# AstroEQ_PTH_V4_8.net
KiCad netlist of a schematic drawn in EAGLE
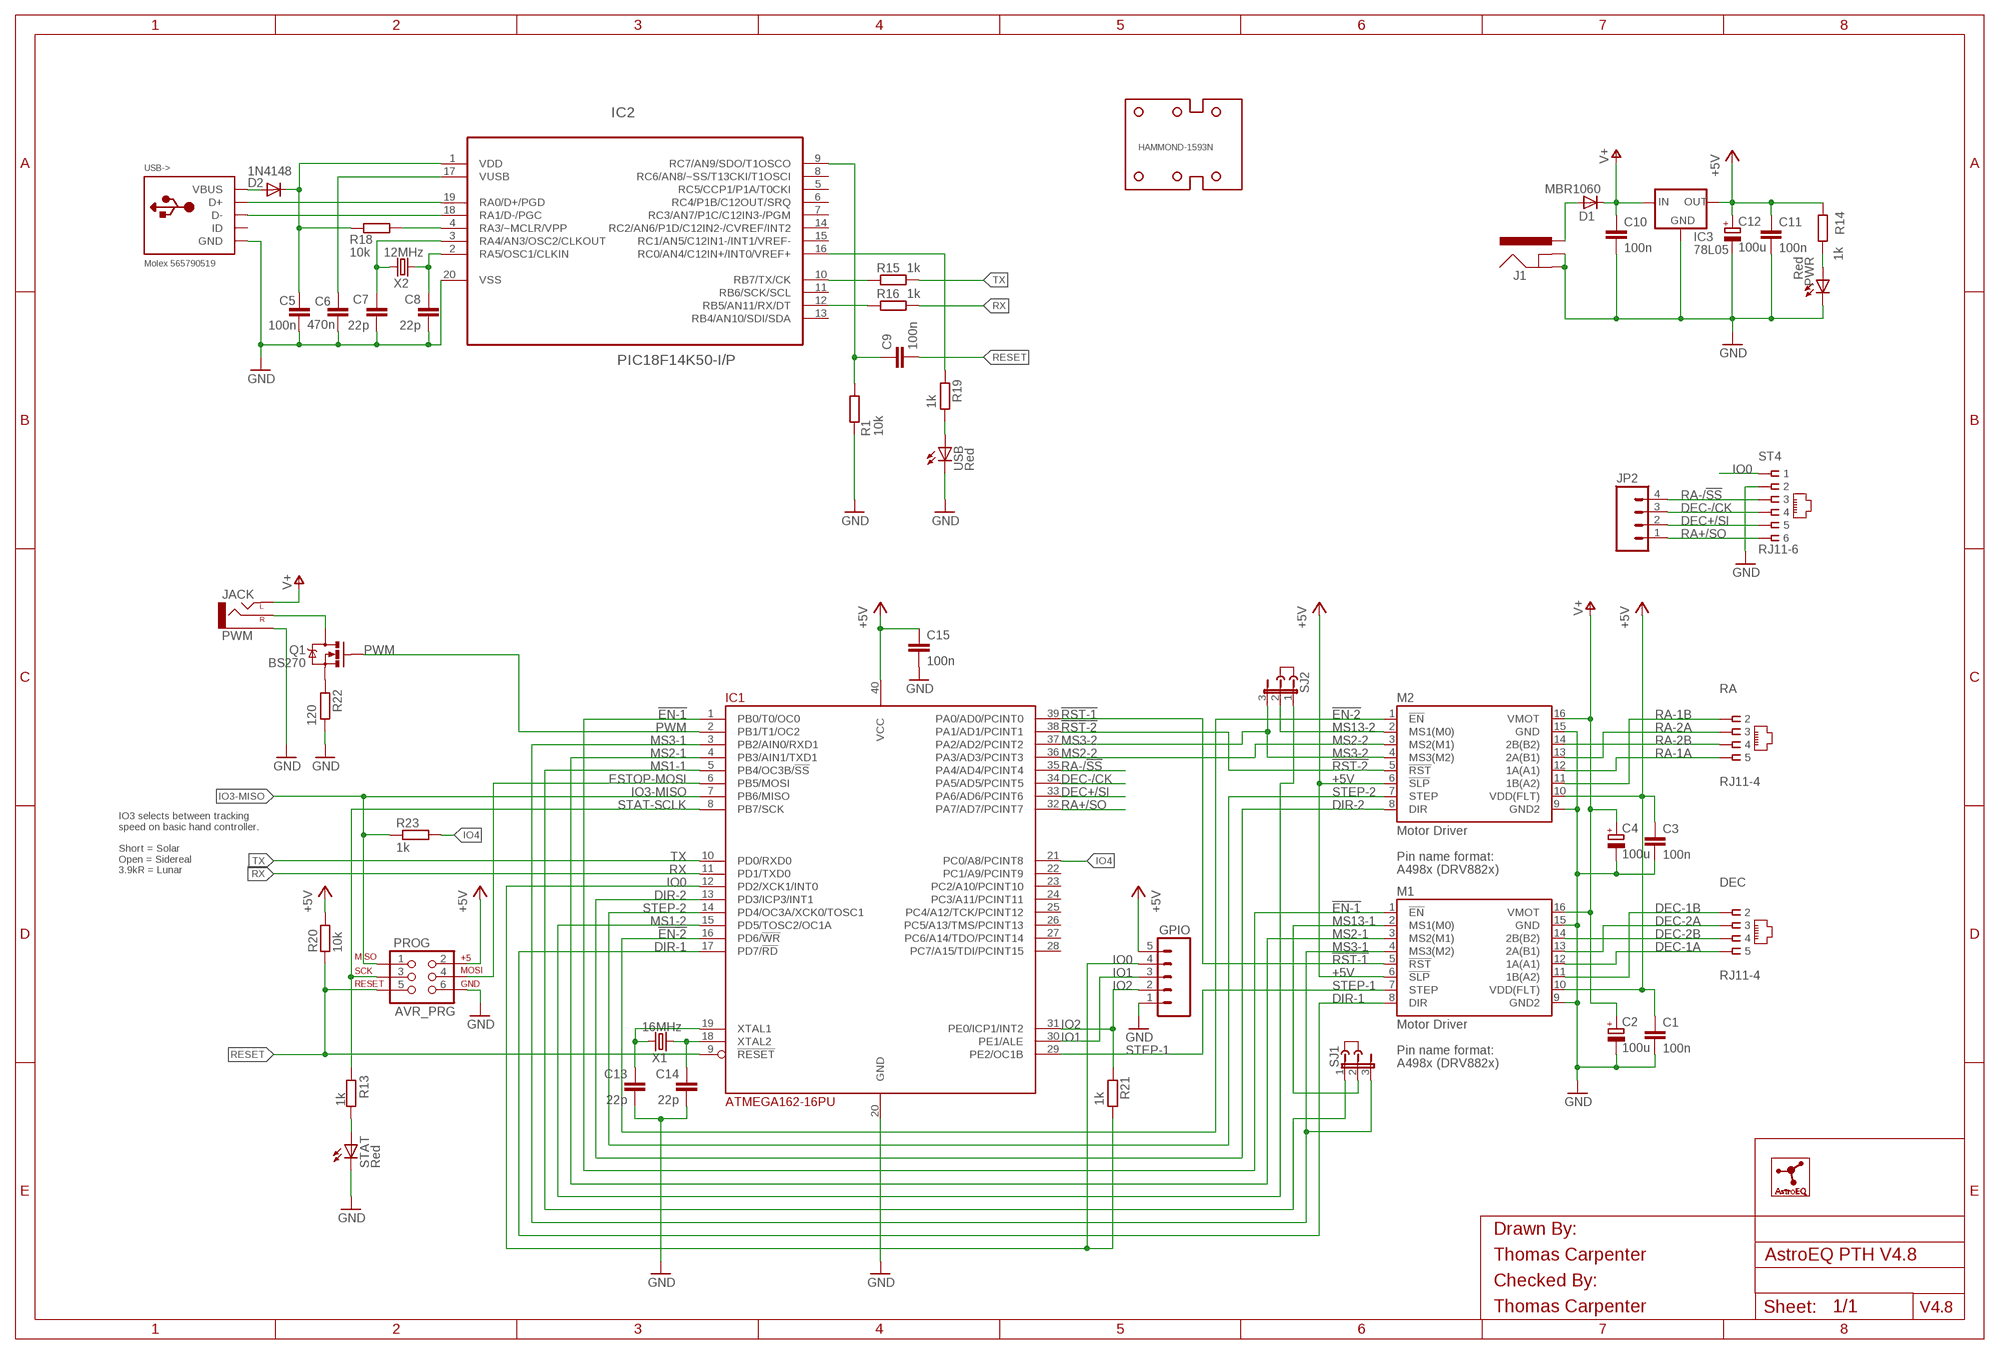
[diagram p0: schematic, sheet 1]

(export (version "E")
  (design (tool "Eeschema 10.0.6"))
  (components
    (comp (ref "C1")
      (value "100n")
      (footprint "eagle-import:C025-024X044")
      (fields (field (name "MF") "AVX") (field (name "MPN") "SR205C104KAR"))
      (libsource (lib "eagle-import") (part "C-EU025-024X044"))
    )
    (comp (ref "C2")
      (value "100u")
      (footprint "eagle-import:E2,5-7")
      (fields (field (name "MF") "MULTICOMP") (field (name "MPN") "MCGPR25V107M6.3X11"))
      (libsource (lib "eagle-import") (part "CPOL-EUE2.5-7"))
    )
    (comp (ref "C3")
      (value "100n")
      (footprint "eagle-import:C025-024X044")
      (fields (field (name "MF") "AVX") (field (name "MPN") "SR205C104KAR"))
      (libsource (lib "eagle-import") (part "C-EU025-024X044"))
    )
    (comp (ref "C4")
      (value "100u")
      (footprint "eagle-import:E2,5-7")
      (fields (field (name "MF") "MULTICOMP") (field (name "MPN") "MCGPR25V107M6.3X11"))
      (libsource (lib "eagle-import") (part "CPOL-EUE2.5-7"))
    )
    (comp (ref "C5")
      (value "100n")
      (footprint "eagle-import:C025-024X044")
      (fields (field (name "MF") "AVX") (field (name "MPN") "SR205C104KAR"))
      (libsource (lib "eagle-import") (part "C-EU025-024X044"))
    )
    (comp (ref "C6")
      (value "470n")
      (footprint "eagle-import:C025-024X044")
      (fields (field (name "MF") "KEMET") (field (name "MPN") "C320C474M5U5TA"))
      (libsource (lib "eagle-import") (part "C-EU025-024X044"))
    )
    (comp (ref "C7")
      (value "22p")
      (footprint "eagle-import:C025-024X044")
      (fields (field (name "MF") "AVX") (field (name "MPN") "SR151A220JAR"))
      (libsource (lib "eagle-import") (part "C-EU025-024X044"))
    )
    (comp (ref "C8")
      (value "22p")
      (footprint "eagle-import:C025-024X044")
      (fields (field (name "MF") "AVX") (field (name "MPN") "SR151A220JAR"))
      (libsource (lib "eagle-import") (part "C-EU025-024X044"))
    )
    (comp (ref "C9")
      (value "100n")
      (footprint "eagle-import:C025-024X044")
      (fields (field (name "MF") "AVX") (field (name "MPN") "SR205C104KAR"))
      (libsource (lib "eagle-import") (part "C-EU025-024X044"))
    )
    (comp (ref "C10")
      (value "100n")
      (footprint "eagle-import:C025-024X044")
      (fields (field (name "MF") "AVX") (field (name "MPN") "SR205C104KAR"))
      (libsource (lib "eagle-import") (part "C-EU025-024X044"))
    )
    (comp (ref "C11")
      (value "100n")
      (footprint "eagle-import:C025-024X044")
      (fields (field (name "MF") "AVX") (field (name "MPN") "SR205C104KAR"))
      (libsource (lib "eagle-import") (part "C-EU025-024X044"))
    )
    (comp (ref "C12")
      (value "100u")
      (footprint "eagle-import:E2,5-7")
      (fields (field (name "MF") "MULTICOMP") (field (name "MPN") "MCGPR25V107M6.3X11"))
      (libsource (lib "eagle-import") (part "CPOL-EUE2.5-7"))
    )
    (comp (ref "C13")
      (value "22p")
      (footprint "eagle-import:C025-024X044")
      (fields (field (name "MF") "AVX") (field (name "MPN") "SR151A220JAR"))
      (libsource (lib "eagle-import") (part "C-EU025-024X044"))
    )
    (comp (ref "C14")
      (value "22p")
      (footprint "eagle-import:C025-024X044")
      (fields (field (name "MF") "AVX") (field (name "MPN") "SR151A220JAR"))
      (libsource (lib "eagle-import") (part "C-EU025-024X044"))
    )
    (comp (ref "C15")
      (value "100n")
      (footprint "eagle-import:C025-024X044")
      (fields (field (name "MF") "AVX") (field (name "MPN") "SR205C104KAR"))
      (libsource (lib "eagle-import") (part "C-EU025-024X044"))
    )
    (comp (ref "D1")
      (value "MBR1060")
      (footprint "eagle-import:C221B1A")
      (fields (field (name "MF") "MULTICOMP"))
      (libsource (lib "eagle-import") (part "MUR820"))
    )
    (comp (ref "D2")
      (value "1N4148")
      (footprint "eagle-import:DIODE-1N4148")
      (fields (field (name "MF") "MULTICOMP") (field (name "MPN") "1N4148."))
      (libsource (lib "eagle-import") (part "DIODE1N4148"))
    )
    (comp (ref "DEC")
      (value "RJ11-4")
      (footprint "eagle-import:RJ11-NO_SHIELD-4")
      (fields (field (name "MF") "MOLEX") (field (name "MPN") "95501-2641"))
      (libsource (lib "eagle-import") (part "RJ11-4"))
    )
    (comp (ref "GPIO")
      (value "M05PTH")
      (footprint "eagle-import:1X05")
      (fields (field (name "MF") "CYNERGY3") (field (name "MPN") "SSF211X050"))
      (libsource (lib "eagle-import") (part "M05PTH"))
    )
    (comp (ref "HAMMOND-1593N")
      (value "HAMMOND-1593N-4HOLE")
      (footprint "eagle-import:HAMMOND-1593N4HOLES")
      (fields (field (name "MF") "HAMMOND") (field (name "MPN") "1593NBK"))
      (libsource (lib "eagle-import") (part "HAMMOND-1593N-4HOLE"))
    )
    (comp (ref "IC1")
      (value "ATMEGA162-16PU")
      (footprint "eagle-import:DIL40")
      (fields (field (name "MF") "ATMEL"))
      (libsource (lib "eagle-import") (part "ATMEGA162-16PU"))
    )
    (comp (ref "IC2")
      (value "PIC18F14K50-I/P")
      (footprint "eagle-import:DIL20")
      (fields (field (name "MF") "MICROCHIP"))
      (libsource (lib "eagle-import") (part "PIC18F14K50-I/P"))
    )
    (comp (ref "IC3")
      (value "78L05")
      (footprint "eagle-import:TO-92")
      (fields (field (name "MF") "FAIRCHILD SEMICONDUCTOR") (field (name "MPN") "LM78L05ACZX"))
      (libsource (lib "eagle-import") (part "V_REG_78XXTO-92"))
    )
    (comp (ref "J1")
      (value "POWER_JACKPTH")
      (footprint "eagle-import:POWER_JACK_PTH")
      (fields (field (name "MF") "MULTICOMP") (field (name "MPN") "MJ-179PH"))
      (libsource (lib "eagle-import") (part "POWER_JACKPTH"))
    )
    (comp (ref "J2")
      (value "JUMPER")
      (footprint "eagle-import:JUMP")
      (libsource (lib "eagle-import") (part "JUMPER"))
    )
    (comp (ref "J3")
      (value "JUMPER")
      (footprint "eagle-import:JUMP")
      (libsource (lib "eagle-import") (part "JUMPER"))
    )
    (comp (ref "JP2")
      (value "M04PTH")
      (footprint "eagle-import:1X04")
      (libsource (lib "eagle-import") (part "M04PTH"))
    )
    (comp (ref "LOGO1")
      (value "ASTROEQ5MM")
      (footprint "eagle-import:ASTROEQ-SMALL")
      (libsource (lib "eagle-import") (part "ASTROEQ5MM"))
    )
    (comp (ref "M1")
      (value "Motor Driver")
      (footprint "eagle-import:DIP16-W")
      (fields (field (name "MF") "SAMTEC") (field (name "MPN") "CES-116-01-T-S"))
      (libsource (lib "eagle-import") (part "A4983CARRIER"))
    )
    (comp (ref "M2")
      (value "Motor Driver")
      (footprint "eagle-import:DIP16-W")
      (fields (field (name "MF") "SAMTEC") (field (name "MPN") "CES-116-01-T-S"))
      (libsource (lib "eagle-import") (part "A4983CARRIER"))
    )
    (comp (ref "PROG")
      (value "AVR_PRG")
      (footprint "eagle-import:2X3")
      (fields (field (name "MF") "TE CONNECTIVITY / AMP") (field (name "MPN") "826632-3"))
      (libsource (lib "eagle-import") (part "AVR_SPI_PRG_6PTH"))
    )
    (comp (ref "PWM")
      (value "JACK")
      (footprint "eagle-import:AUDIO-JACK")
      (fields (field (name "MF") "CLIFF ELECTRONIC COMPONENTS") (field (name "MPN") "FC68131"))
      (libsource (lib "eagle-import") (part "AUDIO-JACKPTH"))
    )
    (comp (ref "PWR")
      (value "Red")
      (footprint "eagle-import:LED3MM")
      (fields (field (name "MF") "KINGBRIGHT") (field (name "MPN") "L-424HDT"))
      (libsource (lib "eagle-import") (part "LED3MM"))
    )
    (comp (ref "Q1")
      (value "BS270")
      (footprint "eagle-import:TO-92")
      (fields (field (name "MF") "FAIRCHILD SEMICONDUCTOR"))
      (libsource (lib "eagle-import") (part "MOSFET-NCHANNELPTH"))
    )
    (comp (ref "R1")
      (value "10k")
      (footprint "eagle-import:0204_7")
      (fields (field (name "MF") "MULTICOMP") (field (name "MPN") "MF12 10K"))
      (libsource (lib "eagle-import") (part "R-EU_0204/7"))
    )
    (comp (ref "R13")
      (value "1k")
      (footprint "eagle-import:0204_7")
      (fields (field (name "MF") "MULTICOMP") (field (name "MPN") "MF12 1K"))
      (libsource (lib "eagle-import") (part "R-EU_0204/7"))
    )
    (comp (ref "R14")
      (value "1k")
      (footprint "eagle-import:0204_7")
      (fields (field (name "MF") "MULTICOMP") (field (name "MPN") "MF12 1K"))
      (libsource (lib "eagle-import") (part "R-EU_0204/7"))
    )
    (comp (ref "R15")
      (value "1k")
      (footprint "eagle-import:0204_7")
      (fields (field (name "MF") "MULTICOMP") (field (name "MPN") "MF12 1K"))
      (libsource (lib "eagle-import") (part "R-EU_0204/7"))
    )
    (comp (ref "R16")
      (value "1k")
      (footprint "eagle-import:0204_7")
      (fields (field (name "MF") "MULTICOMP") (field (name "MPN") "MF12 1K"))
      (libsource (lib "eagle-import") (part "R-EU_0204/7"))
    )
    (comp (ref "R18")
      (value "10k")
      (footprint "eagle-import:0204_7")
      (fields (field (name "MF") "MULTICOMP") (field (name "MPN") "MF12 10K"))
      (libsource (lib "eagle-import") (part "R-EU_0204/7"))
    )
    (comp (ref "R19")
      (value "1k")
      (footprint "eagle-import:0204_7")
      (fields (field (name "MF") "MULTICOMP") (field (name "MPN") "MF12 1K"))
      (libsource (lib "eagle-import") (part "R-EU_0204/7"))
    )
    (comp (ref "R20")
      (value "10k")
      (footprint "eagle-import:0204_7")
      (fields (field (name "MF") "MULTICOMP") (field (name "MPN") "MF12 10K"))
      (libsource (lib "eagle-import") (part "R-EU_0204/7"))
    )
    (comp (ref "R21")
      (value "1k")
      (footprint "eagle-import:0204_7")
      (fields (field (name "MF") "MULTICOMP") (field (name "MPN") "MF12 1K"))
      (libsource (lib "eagle-import") (part "R-EU_0204/7"))
    )
    (comp (ref "R22")
      (value "120")
      (footprint "eagle-import:0204_7")
      (fields (field (name "MF") "MULTICOMP") (field (name "MPN") "MF12 120R"))
      (libsource (lib "eagle-import") (part "R-EU_0204/7"))
    )
    (comp (ref "R23")
      (value "1k")
      (footprint "eagle-import:0207_10")
      (fields (field (name "MF") "MULTICOMP") (field (name "MPN") "MF12 1K"))
      (libsource (lib "eagle-import") (part "R-EU_0207/10"))
    )
    (comp (ref "RA")
      (value "RJ11-4")
      (footprint "eagle-import:RJ11-NO_SHIELD-4")
      (fields (field (name "MF") "MOLEX") (field (name "MPN") "95501-2641"))
      (libsource (lib "eagle-import") (part "RJ11-4"))
    )
    (comp (ref "SJ1")
      (value "JP2EL")
      (footprint "eagle-import:JP2L")
      (libsource (lib "eagle-import") (part "JP2EL"))
    )
    (comp (ref "SJ2")
      (value "JP2EL")
      (footprint "eagle-import:JP2L")
      (libsource (lib "eagle-import") (part "JP2EL"))
    )
    (comp (ref "ST4")
      (value "RJ11-6")
      (footprint "eagle-import:RJ11-NO_SHIELD")
      (fields
        (field (name "MF") "TYCO ELECTRONICS")
        (field (name "MPN") "RJ11-2L-B")
        (field (name "MF_1") "MOLEX")
        (field (name "MPN_1") "95501-2661")
        (field (name "OC_FARNELL") "1536490")
      )
      (libsource (lib "eagle-import") (part "RJ11-2L-B"))
    )
    (comp (ref "STAT")
      (value "Red")
      (footprint "eagle-import:LED3MM")
      (fields (field (name "MF") "KINGBRIGHT") (field (name "MPN") "L-424HDT"))
      (libsource (lib "eagle-import") (part "LED3MM"))
    )
    (comp (ref "USB")
      (value "Red")
      (footprint "eagle-import:LED3MM")
      (fields (field (name "MF") "KINGBRIGHT") (field (name "MPN") "L-424HDT"))
      (libsource (lib "eagle-import") (part "LED3MM"))
    )
    (comp (ref "USB->")
      (value "Molex 565790519")
      (footprint "eagle-import:USB-MINIB-THM-MOLEX")
      (fields (field (name "MF") "MOLEX") (field (name "MPN") "565790519"))
      (libsource (lib "eagle-import") (part "USBMOLEX"))
    )
    (comp (ref "X1")
      (value "16MHz")
      (footprint "eagle-import:HC49US")
      (fields (field (name "MF") "TXC") (field (name "MPN") "9B-16.000MEEJ-B"))
      (libsource (lib "eagle-import") (part "CRYSTALHC49US"))
    )
    (comp (ref "X2")
      (value "12MHz")
      (footprint "eagle-import:HC49US")
      (fields (field (name "MF") "TXC") (field (name "MPN") "9B-12.000MAAJ-B"))
      (libsource (lib "eagle-import") (part "CRYSTALHC49US"))
    )
  )
  (nets
    (net (code "1") (name "+5V") (class "Default")
      (node (ref "C1") (pin "1") (pinfunction "1_1") (pintype "passive"))
      (node (ref "C11") (pin "1") (pinfunction "1_1") (pintype "passive"))
      (node (ref "C12") (pin "+") (pinfunction "+_+") (pintype "passive"))
      (node (ref "C15") (pin "1") (pinfunction "1_1") (pintype "passive"))
      (node (ref "C3") (pin "1") (pinfunction "1_1") (pintype "passive"))
      (node (ref "GPIO") (pin "5") (pinfunction "5_5") (pintype "passive"))
      (node (ref "IC1") (pin "40") (pinfunction "VCC_40") (pintype "power_in"))
      (node (ref "IC3") (pin "1") (pinfunction "OUT_1") (pintype "power_in"))
      (node (ref "M1") (pin "10") (pinfunction "VDD(FLT)_10") (pintype "power_in"))
      (node (ref "M1") (pin "6") (pinfunction "~{SLP}_6") (pintype "input"))
      (node (ref "M2") (pin "10") (pinfunction "VDD(FLT)_10") (pintype "power_in"))
      (node (ref "M2") (pin "6") (pinfunction "~{SLP}_6") (pintype "input"))
      (node (ref "PROG") (pin "2") (pinfunction "2_2") (pintype "passive"))
      (node (ref "R14") (pin "1") (pinfunction "1_1") (pintype "passive"))
      (node (ref "R20") (pin "2") (pinfunction "2_2") (pintype "passive"))
    )
    (net (code "2") (name "/DEC+{slash}SI") (class "Default")
      (node (ref "IC1") (pin "33") (pinfunction "PA6/AD6/PCINT6_33") (pintype "bidirectional"))
      (node (ref "JP2") (pin "2") (pinfunction "2_2") (pintype "passive"))
      (node (ref "ST4") (pin "5") (pinfunction "5_5") (pintype "passive"))
    )
    (net (code "3") (name "/DEC-1A") (class "Default")
      (node (ref "DEC") (pin "5") (pinfunction "5_5") (pintype "passive"))
      (node (ref "M1") (pin "12") (pinfunction "1A(A1)_12") (pintype "output"))
    )
    (net (code "4") (name "/DEC-1B") (class "Default")
      (node (ref "DEC") (pin "2") (pinfunction "2_2") (pintype "passive"))
      (node (ref "M1") (pin "11") (pinfunction "1B(A2)_11") (pintype "output"))
    )
    (net (code "5") (name "/DEC-2A") (class "Default")
      (node (ref "DEC") (pin "3") (pinfunction "3_3") (pintype "passive"))
      (node (ref "M1") (pin "13") (pinfunction "2A(B1)_13") (pintype "output"))
    )
    (net (code "6") (name "/DEC-2B") (class "Default")
      (node (ref "DEC") (pin "4") (pinfunction "4_4") (pintype "passive"))
      (node (ref "M1") (pin "14") (pinfunction "2B(B2)_14") (pintype "output"))
    )
    (net (code "7") (name "/DEC-{slash}CK") (class "Default")
      (node (ref "IC1") (pin "34") (pinfunction "PA5/AD5/PCINT5_34") (pintype "bidirectional"))
      (node (ref "JP2") (pin "3") (pinfunction "3_3") (pintype "passive"))
      (node (ref "ST4") (pin "4") (pinfunction "4_4") (pintype "passive"))
    )
    (net (code "8") (name "/DIR-1") (class "Default")
      (node (ref "IC1") (pin "17") (pinfunction "PD7/~{RD}_17") (pintype "bidirectional"))
      (node (ref "M1") (pin "8") (pinfunction "DIR_8") (pintype "input"))
    )
    (net (code "9") (name "/DIR-2") (class "Default")
      (node (ref "IC1") (pin "13") (pinfunction "PD3/ICP3/INT1_13") (pintype "bidirectional"))
      (node (ref "M2") (pin "8") (pinfunction "DIR_8") (pintype "input"))
    )
    (net (code "10") (name "/ESTOP-MOSI") (class "Default")
      (node (ref "IC1") (pin "6") (pinfunction "PB5/MOSI_6") (pintype "bidirectional"))
      (node (ref "PROG") (pin "4") (pinfunction "4_4") (pintype "passive"))
    )
    (net (code "11") (name "/IO0") (class "Default")
      (node (ref "GPIO") (pin "4") (pinfunction "4_4") (pintype "passive"))
      (node (ref "IC1") (pin "12") (pinfunction "PD2/XCK1/INT0_12") (pintype "bidirectional"))
      (node (ref "R21") (pin "1") (pinfunction "1_1") (pintype "passive"))
      (node (ref "ST4") (pin "1") (pinfunction "1_1") (pintype "passive"))
    )
    (net (code "12") (name "/IO1") (class "Default")
      (node (ref "GPIO") (pin "3") (pinfunction "3_3") (pintype "passive"))
      (node (ref "IC1") (pin "30") (pinfunction "PE1/ALE_30") (pintype "bidirectional"))
    )
    (net (code "13") (name "/IO2") (class "Default")
      (node (ref "GPIO") (pin "2") (pinfunction "2_2") (pintype "passive"))
      (node (ref "IC1") (pin "31") (pinfunction "PE0/ICP1/INT2_31") (pintype "bidirectional"))
      (node (ref "R21") (pin "2") (pinfunction "2_2") (pintype "passive"))
    )
    (net (code "14") (name "/MS1-1") (class "Default")
      (node (ref "IC1") (pin "5") (pinfunction "PB4/OC3B/~{SS}_5") (pintype "bidirectional"))
      (node (ref "SJ1") (pin "1") (pinfunction "1_1") (pintype "passive"))
    )
    (net (code "15") (name "/MS1-2") (class "Default")
      (node (ref "IC1") (pin "15") (pinfunction "PD5/TOSC2/OC1A_15") (pintype "bidirectional"))
      (node (ref "SJ2") (pin "1") (pinfunction "1_1") (pintype "passive"))
    )
    (net (code "16") (name "/MS2-1") (class "Default")
      (node (ref "IC1") (pin "4") (pinfunction "PB3/AIN1/TXD1_4") (pintype "bidirectional"))
      (node (ref "M1") (pin "3") (pinfunction "MS2(M1)_3") (pintype "input"))
    )
    (net (code "17") (name "/MS2-2") (class "Default")
      (node (ref "IC1") (pin "36") (pinfunction "PA3/AD3/PCINT3_36") (pintype "bidirectional"))
      (node (ref "M2") (pin "3") (pinfunction "MS2(M1)_3") (pintype "input"))
    )
    (net (code "18") (name "/MS3-1") (class "Default")
      (node (ref "IC1") (pin "3") (pinfunction "PB2/AIN0/RXD1_3") (pintype "bidirectional"))
      (node (ref "M1") (pin "4") (pinfunction "MS3(M2)_4") (pintype "input"))
      (node (ref "SJ1") (pin "3") (pinfunction "3_3") (pintype "passive"))
    )
    (net (code "19") (name "/MS3-2") (class "Default")
      (node (ref "IC1") (pin "37") (pinfunction "PA2/AD2/PCINT2_37") (pintype "bidirectional"))
      (node (ref "M2") (pin "4") (pinfunction "MS3(M2)_4") (pintype "input"))
      (node (ref "SJ2") (pin "3") (pinfunction "3_3") (pintype "passive"))
    )
    (net (code "20") (name "/MS13-1") (class "Default")
      (node (ref "M1") (pin "2") (pinfunction "MS1(M0)_2") (pintype "input"))
      (node (ref "SJ1") (pin "2") (pinfunction "2_2") (pintype "passive"))
    )
    (net (code "21") (name "/MS13-2") (class "Default")
      (node (ref "M2") (pin "2") (pinfunction "MS1(M0)_2") (pintype "input"))
      (node (ref "SJ2") (pin "2") (pinfunction "2_2") (pintype "passive"))
    )
    (net (code "22") (name "/PWM") (class "Default")
      (node (ref "IC1") (pin "2") (pinfunction "PB1/T1/OC2_2") (pintype "bidirectional"))
      (node (ref "Q1") (pin "2") (pinfunction "G_2") (pintype "passive"))
    )
    (net (code "23") (name "/RA+{slash}SO") (class "Default")
      (node (ref "IC1") (pin "32") (pinfunction "PA7/AD7/PCINT7_32") (pintype "bidirectional"))
      (node (ref "JP2") (pin "1") (pinfunction "1_1") (pintype "passive"))
      (node (ref "ST4") (pin "6") (pinfunction "6_6") (pintype "passive"))
    )
    (net (code "24") (name "/RA-1A") (class "Default")
      (node (ref "M2") (pin "12") (pinfunction "1A(A1)_12") (pintype "output"))
      (node (ref "RA") (pin "5") (pinfunction "5_5") (pintype "passive"))
    )
    (net (code "25") (name "/RA-1B") (class "Default")
      (node (ref "M2") (pin "11") (pinfunction "1B(A2)_11") (pintype "output"))
      (node (ref "RA") (pin "2") (pinfunction "2_2") (pintype "passive"))
    )
    (net (code "26") (name "/RA-2A") (class "Default")
      (node (ref "M2") (pin "13") (pinfunction "2A(B1)_13") (pintype "output"))
      (node (ref "RA") (pin "3") (pinfunction "3_3") (pintype "passive"))
    )
    (net (code "27") (name "/RA-2B") (class "Default")
      (node (ref "M2") (pin "14") (pinfunction "2B(B2)_14") (pintype "output"))
      (node (ref "RA") (pin "4") (pinfunction "4_4") (pintype "passive"))
    )
    (net (code "28") (name "/RA-{slash}~{SS}") (class "Default")
      (node (ref "IC1") (pin "35") (pinfunction "PA4/AD4/PCINT4_35") (pintype "bidirectional"))
      (node (ref "JP2") (pin "4") (pinfunction "4_4") (pintype "passive"))
      (node (ref "ST4") (pin "3") (pinfunction "3_3") (pintype "passive"))
    )
    (net (code "29") (name "/STAT-SCLK") (class "Default")
      (node (ref "IC1") (pin "8") (pinfunction "PB7/SCK_8") (pintype "bidirectional"))
      (node (ref "PROG") (pin "3") (pinfunction "3_3") (pintype "passive"))
      (node (ref "R13") (pin "1") (pinfunction "1_1") (pintype "passive"))
    )
    (net (code "30") (name "/STEP-1") (class "Default")
      (node (ref "IC1") (pin "29") (pinfunction "PE2/OC1B_29") (pintype "bidirectional"))
      (node (ref "M1") (pin "7") (pinfunction "STEP_7") (pintype "input"))
    )
    (net (code "31") (name "/STEP-2") (class "Default")
      (node (ref "IC1") (pin "14") (pinfunction "PD4/OC3A/XCK0/TOSC1_14") (pintype "bidirectional"))
      (node (ref "M2") (pin "7") (pinfunction "STEP_7") (pintype "input"))
    )
    (net (code "32") (name "/~{EN-1}") (class "Default")
      (node (ref "IC1") (pin "1") (pinfunction "PB0/T0/OC0_1") (pintype "bidirectional"))
      (node (ref "M1") (pin "1") (pinfunction "~{EN}_1") (pintype "input"))
    )
    (net (code "33") (name "/~{EN-2}") (class "Default")
      (node (ref "IC1") (pin "16") (pinfunction "PD6/~{WR}_16") (pintype "bidirectional"))
      (node (ref "M2") (pin "1") (pinfunction "~{EN}_1") (pintype "input"))
    )
    (net (code "34") (name "/~{RST-1}") (class "Default")
      (node (ref "IC1") (pin "39") (pinfunction "PA0/AD0/PCINT0_39") (pintype "bidirectional"))
      (node (ref "M1") (pin "5") (pinfunction "~{RST}_5") (pintype "input"))
    )
    (net (code "35") (name "/~{RST-2}") (class "Default")
      (node (ref "IC1") (pin "38") (pinfunction "PA1/AD1/PCINT1_38") (pintype "bidirectional"))
      (node (ref "M2") (pin "5") (pinfunction "~{RST}_5") (pintype "input"))
    )
    (net (code "36") (name "GND") (class "Default")
      (node (ref "C1") (pin "2") (pinfunction "2_2") (pintype "passive"))
      (node (ref "C10") (pin "2") (pinfunction "2_2") (pintype "passive"))
      (node (ref "C11") (pin "2") (pinfunction "2_2") (pintype "passive"))
      (node (ref "C12") (pin "-") (pinfunction "-_-") (pintype "passive"))
      (node (ref "C13") (pin "2") (pinfunction "2_2") (pintype "passive"))
      (node (ref "C14") (pin "2") (pinfunction "2_2") (pintype "passive"))
      (node (ref "C15") (pin "2") (pinfunction "2_2") (pintype "passive"))
      (node (ref "C2") (pin "-") (pinfunction "-_-") (pintype "passive"))
      (node (ref "C3") (pin "2") (pinfunction "2_2") (pintype "passive"))
      (node (ref "C4") (pin "-") (pinfunction "-_-") (pintype "passive"))
      (node (ref "C5") (pin "2") (pinfunction "2_2") (pintype "passive"))
      (node (ref "C6") (pin "1") (pinfunction "1_1") (pintype "passive"))
      (node (ref "C7") (pin "2") (pinfunction "2_2") (pintype "passive"))
      (node (ref "C8") (pin "2") (pinfunction "2_2") (pintype "passive"))
      (node (ref "GPIO") (pin "1") (pinfunction "1_1") (pintype "passive"))
      (node (ref "IC1") (pin "20") (pinfunction "GND_20") (pintype "power_in"))
      (node (ref "IC2") (pin "20") (pinfunction "VSS_20") (pintype "power_in"))
      (node (ref "IC3") (pin "2") (pinfunction "GND_2") (pintype "input"))
      (node (ref "J1") (pin "GND") (pinfunction "GND_GND") (pintype "bidirectional"))
      (node (ref "J1") (pin "GNDBREAK") (pinfunction "GNDBREAK_GNDBREAK") (pintype "bidirectional"))
      (node (ref "M1") (pin "15") (pinfunction "GND_15") (pintype "power_in"))
      (node (ref "M1") (pin "9") (pinfunction "GND2_9") (pintype "power_in"))
      (node (ref "M2") (pin "15") (pinfunction "GND_15") (pintype "power_in"))
      (node (ref "M2") (pin "9") (pinfunction "GND2_9") (pintype "power_in"))
      (node (ref "PROG") (pin "6") (pinfunction "6_6") (pintype "passive"))
      (node (ref "PWM") (pin "SLEEVE") (pinfunction "SLEEVE_SLEEVE") (pintype "bidirectional"))
      (node (ref "PWR") (pin "K") (pinfunction "C_K") (pintype "passive"))
      (node (ref "R1") (pin "2") (pinfunction "2_2") (pintype "passive"))
      (node (ref "R22") (pin "1") (pinfunction "1_1") (pintype "passive"))
      (node (ref "ST4") (pin "2") (pinfunction "2_2") (pintype "passive"))
      (node (ref "STAT") (pin "K") (pinfunction "C_K") (pintype "passive"))
      (node (ref "USB") (pin "K") (pinfunction "C_K") (pintype "passive"))
      (node (ref "USB->") (pin "GND") (pinfunction "GND_GND") (pintype "power_in"))
      (node (ref "USB->") (pin "GND1") (pinfunction "GND_GND1") (pintype "power_in"))
      (node (ref "USB->") (pin "GND4") (pinfunction "GND_GND4") (pintype "power_in"))
    )
    (net (code "37") (name "IO3-MISO") (class "Default")
      (node (ref "IC1") (pin "7") (pinfunction "PB6/MISO_7") (pintype "bidirectional"))
      (node (ref "PROG") (pin "1") (pinfunction "1_1") (pintype "passive"))
      (node (ref "R23") (pin "1") (pinfunction "1_1") (pintype "passive"))
    )
    (net (code "38") (name "IO4") (class "Default")
      (node (ref "IC1") (pin "21") (pinfunction "PC0/A8/PCINT8_21") (pintype "bidirectional"))
      (node (ref "R23") (pin "2") (pinfunction "2_2") (pintype "passive"))
    )
    (net (code "39") (name "Net-(D1-PadA)") (class "Default")
      (node (ref "D1") (pin "A") (pinfunction "A_A") (pintype "passive"))
      (node (ref "J1") (pin "PWR") (pinfunction "PWR_PWR") (pintype "bidirectional"))
    )
    (net (code "40") (name "Net-(D2-PadA)") (class "Default")
      (node (ref "D2") (pin "A") (pinfunction "A_A") (pintype "passive"))
      (node (ref "USB->") (pin "VBUS") (pinfunction "VBUS_VBUS") (pintype "power_in"))
    )
    (net (code "41") (name "Net-(IC1-XTAL1)") (class "Default")
      (node (ref "C13") (pin "1") (pinfunction "1_1") (pintype "passive"))
      (node (ref "IC1") (pin "19") (pinfunction "XTAL1_19") (pintype "input"))
      (node (ref "X1") (pin "2") (pinfunction "2_2") (pintype "passive"))
    )
    (net (code "42") (name "Net-(IC1-XTAL2)") (class "Default")
      (node (ref "C14") (pin "1") (pinfunction "1_1") (pintype "passive"))
      (node (ref "IC1") (pin "18") (pinfunction "XTAL2_18") (pintype "input"))
      (node (ref "X1") (pin "1") (pinfunction "1_1") (pintype "passive"))
    )
    (net (code "43") (name "Net-(IC2-RA0{slash}D+{slash}PGD)") (class "Default")
      (node (ref "IC2") (pin "19") (pinfunction "RA0/D+/PGD_19") (pintype "bidirectional"))
      (node (ref "USB->") (pin "D+") (pinfunction "D+_D+") (pintype "bidirectional"))
    )
    (net (code "44") (name "Net-(IC2-RA1{slash}D-{slash}PGC)") (class "Default")
      (node (ref "IC2") (pin "18") (pinfunction "RA1/D-/PGC_18") (pintype "bidirectional"))
      (node (ref "USB->") (pin "D-") (pinfunction "D-_D-") (pintype "bidirectional"))
    )
    (net (code "45") (name "Net-(IC2-RA3{slash}~{MCLR{slash}VPP})") (class "Default")
      (node (ref "IC2") (pin "4") (pinfunction "RA3/~{MCLR/VPP}_4") (pintype "input"))
      (node (ref "R18") (pin "1") (pinfunction "1_1") (pintype "passive"))
    )
    (net (code "46") (name "Net-(IC2-RA4{slash}AN3{slash}OSC2{slash}CLKOUT)") (class "Default")
      (node (ref "C7") (pin "1") (pinfunction "1_1") (pintype "passive"))
      (node (ref "IC2") (pin "3") (pinfunction "RA4/AN3/OSC2/CLKOUT_3") (pintype "bidirectional"))
      (node (ref "X2") (pin "2") (pinfunction "2_2") (pintype "passive"))
    )
    (net (code "47") (name "Net-(IC2-RA5{slash}OSC1{slash}CLKIN)") (class "Default")
      (node (ref "C8") (pin "1") (pinfunction "1_1") (pintype "passive"))
      (node (ref "IC2") (pin "2") (pinfunction "RA5/OSC1/CLKIN_2") (pintype "bidirectional"))
      (node (ref "X2") (pin "1") (pinfunction "1_1") (pintype "passive"))
    )
    (net (code "48") (name "Net-(IC2-RB5{slash}AN11{slash}RX{slash}DT)") (class "Default")
      (node (ref "IC2") (pin "12") (pinfunction "RB5/AN11/RX/DT_12") (pintype "bidirectional"))
      (node (ref "R16") (pin "2") (pinfunction "2_2") (pintype "passive"))
    )
    (net (code "49") (name "Net-(IC2-RB7{slash}TX{slash}CK)") (class "Default")
      (node (ref "IC2") (pin "10") (pinfunction "RB7/TX/CK_10") (pintype "bidirectional"))
      (node (ref "R15") (pin "2") (pinfunction "2_2") (pintype "passive"))
    )
    (net (code "50") (name "Net-(IC2-RC0{slash}AN4{slash}C12IN+{slash}INT0{slash}VREF+)") (class "Default")
      (node (ref "IC2") (pin "16") (pinfunction "RC0/AN4/C12IN+/INT0/VREF+_16") (pintype "bidirectional"))
      (node (ref "R19") (pin "2") (pinfunction "2_2") (pintype "passive"))
    )
    (net (code "51") (name "Net-(IC2-RC7{slash}AN9{slash}SDO{slash}T1OSCO)") (class "Default")
      (node (ref "C9") (pin "1") (pinfunction "1_1") (pintype "passive"))
      (node (ref "IC2") (pin "9") (pinfunction "RC7/AN9/SDO/T1OSCO_9") (pintype "bidirectional"))
      (node (ref "R1") (pin "1") (pinfunction "1_1") (pintype "passive"))
    )
    (net (code "52") (name "Net-(IC2-VDD)") (class "Default")
      (node (ref "C5") (pin "1") (pinfunction "1_1") (pintype "passive"))
      (node (ref "D2") (pin "C") (pinfunction "C_C") (pintype "passive"))
      (node (ref "IC2") (pin "1") (pinfunction "VDD_1") (pintype "power_in"))
      (node (ref "R18") (pin "2") (pinfunction "2_2") (pintype "passive"))
    )
    (net (code "53") (name "Net-(IC2-VUSB)") (class "Default")
      (node (ref "C6") (pin "2") (pinfunction "2_2") (pintype "passive"))
      (node (ref "IC2") (pin "17") (pinfunction "VUSB_17") (pintype "power_in"))
    )
    (net (code "54") (name "Net-(PWM-RIGHT)") (class "Default")
      (node (ref "PWM") (pin "RING") (pinfunction "RIGHT_RING") (pintype "bidirectional"))
      (node (ref "Q1") (pin "1") (pinfunction "D_1") (pintype "passive"))
    )
    (net (code "55") (name "Net-(PWR-PadA)") (class "Default")
      (node (ref "PWR") (pin "A") (pinfunction "A_A") (pintype "passive"))
      (node (ref "R14") (pin "2") (pinfunction "2_2") (pintype "passive"))
    )
    (net (code "56") (name "Net-(Q1-S)") (class "Default")
      (node (ref "Q1") (pin "3") (pinfunction "S_3") (pintype "passive"))
      (node (ref "R22") (pin "2") (pinfunction "2_2") (pintype "passive"))
    )
    (net (code "57") (name "Net-(R13-Pad2)") (class "Default")
      (node (ref "R13") (pin "2") (pinfunction "2_2") (pintype "passive"))
      (node (ref "STAT") (pin "A") (pinfunction "A_A") (pintype "passive"))
    )
    (net (code "58") (name "Net-(R19-Pad1)") (class "Default")
      (node (ref "R19") (pin "1") (pinfunction "1_1") (pintype "passive"))
      (node (ref "USB") (pin "A") (pinfunction "A_A") (pintype "passive"))
    )
    (net (code "59") (name "RESET") (class "Default")
      (node (ref "C9") (pin "2") (pinfunction "2_2") (pintype "passive"))
      (node (ref "IC1") (pin "9") (pinfunction "~{RESET}_9") (pintype "input"))
      (node (ref "PROG") (pin "5") (pinfunction "5_5") (pintype "passive"))
      (node (ref "R20") (pin "1") (pinfunction "1_1") (pintype "passive"))
    )
    (net (code "60") (name "RX") (class "Default")
      (node (ref "IC1") (pin "11") (pinfunction "PD1/TXD0_11") (pintype "bidirectional"))
      (node (ref "R16") (pin "1") (pinfunction "1_1") (pintype "passive"))
    )
    (net (code "61") (name "TX") (class "Default")
      (node (ref "IC1") (pin "10") (pinfunction "PD0/RXD0_10") (pintype "bidirectional"))
      (node (ref "R15") (pin "1") (pinfunction "1_1") (pintype "passive"))
    )
    (net (code "62") (name "V+") (class "Default")
      (node (ref "C10") (pin "1") (pinfunction "1_1") (pintype "passive"))
      (node (ref "C2") (pin "+") (pinfunction "+_+") (pintype "passive"))
      (node (ref "C4") (pin "+") (pinfunction "+_+") (pintype "passive"))
      (node (ref "D1") (pin "C") (pinfunction "C_C") (pintype "passive"))
      (node (ref "IC3") (pin "3") (pinfunction "IN_3") (pintype "input"))
      (node (ref "M1") (pin "16") (pinfunction "VMOT_16") (pintype "power_in"))
      (node (ref "M2") (pin "16") (pinfunction "VMOT_16") (pintype "power_in"))
      (node (ref "PWM") (pin "TIP") (pinfunction "LEFT_TIP") (pintype "bidirectional"))
    )
    (net (code "63") (name "unconnected-(IC1-PC1{slash}A9{slash}PCINT9-Pad22)") (class "Default")
      (node (ref "IC1") (pin "22") (pinfunction "PC1/A9/PCINT9_22") (pintype "bidirectional"))
    )
    (net (code "64") (name "unconnected-(IC1-PC2{slash}A10{slash}PCINT10-Pad23)") (class "Default")
      (node (ref "IC1") (pin "23") (pinfunction "PC2/A10/PCINT10_23") (pintype "bidirectional"))
    )
    (net (code "65") (name "unconnected-(IC1-PC3{slash}A11{slash}PCINT11-Pad24)") (class "Default")
      (node (ref "IC1") (pin "24") (pinfunction "PC3/A11/PCINT11_24") (pintype "bidirectional"))
    )
    (net (code "66") (name "unconnected-(IC1-PC4{slash}A12{slash}TCK{slash}PCINT12-Pad25)") (class "Default")
      (node (ref "IC1") (pin "25") (pinfunction "PC4/A12/TCK/PCINT12_25") (pintype "bidirectional"))
    )
    (net (code "67") (name "unconnected-(IC1-PC5{slash}A13{slash}TMS{slash}PCINT13-Pad26)") (class "Default")
      (node (ref "IC1") (pin "26") (pinfunction "PC5/A13/TMS/PCINT13_26") (pintype "bidirectional"))
    )
    (net (code "68") (name "unconnected-(IC1-PC6{slash}A14{slash}TDO{slash}PCINT14-Pad27)") (class "Default")
      (node (ref "IC1") (pin "27") (pinfunction "PC6/A14/TDO/PCINT14_27") (pintype "bidirectional"))
    )
    (net (code "69") (name "unconnected-(IC1-PC7{slash}A15{slash}TDI{slash}PCINT15-Pad28)") (class "Default")
      (node (ref "IC1") (pin "28") (pinfunction "PC7/A15/TDI/PCINT15_28") (pintype "bidirectional"))
    )
    (net (code "70") (name "unconnected-(IC2-RB4{slash}AN10{slash}SDI{slash}SDA-Pad13)") (class "Default")
      (node (ref "IC2") (pin "13") (pinfunction "RB4/AN10/SDI/SDA_13") (pintype "bidirectional"))
    )
    (net (code "71") (name "unconnected-(IC2-RB6{slash}SCK{slash}SCL-Pad11)") (class "Default")
      (node (ref "IC2") (pin "11") (pinfunction "RB6/SCK/SCL_11") (pintype "bidirectional"))
    )
    (net (code "72") (name "unconnected-(IC2-RC1{slash}AN5{slash}C12IN1-{slash}INT1{slash}VREF--Pad15)") (class "Default")
      (node (ref "IC2") (pin "15") (pinfunction "RC1/AN5/C12IN1-/INT1/VREF-_15") (pintype "bidirectional"))
    )
    (net (code "73") (name "unconnected-(IC2-RC2{slash}AN6{slash}P1D{slash}C12IN2-{slash}CVREF{slash}INT2-Pad14)") (class "Default")
      (node (ref "IC2") (pin "14") (pinfunction "RC2/AN6/P1D/C12IN2-/CVREF/INT2_14") (pintype "bidirectional"))
    )
    (net (code "74") (name "unconnected-(IC2-RC3{slash}AN7{slash}P1C{slash}C12IN3-{slash}PGM-Pad7)") (class "Default")
      (node (ref "IC2") (pin "7") (pinfunction "RC3/AN7/P1C/C12IN3-/PGM_7") (pintype "bidirectional"))
    )
    (net (code "75") (name "unconnected-(IC2-RC4{slash}P1B{slash}C12OUT{slash}SRQ-Pad6)") (class "Default")
      (node (ref "IC2") (pin "6") (pinfunction "RC4/P1B/C12OUT/SRQ_6") (pintype "bidirectional"))
    )
    (net (code "76") (name "unconnected-(IC2-RC5{slash}CCP1{slash}P1A{slash}T0CKI-Pad5)") (class "Default")
      (node (ref "IC2") (pin "5") (pinfunction "RC5/CCP1/P1A/T0CKI_5") (pintype "bidirectional"))
    )
    (net (code "77") (name "unconnected-(IC2-RC6{slash}AN8{slash}~{SS{slash}T13CKI{slash}T1OSCI}-Pad8)") (class "Default")
      (node (ref "IC2") (pin "8") (pinfunction "RC6/AN8/~{SS/T13CKI/T1OSCI}_8") (pintype "bidirectional"))
    )
    (net (code "78") (name "unconnected-(USB->-PadID)") (class "Default")
      (node (ref "USB->") (pin "ID") (pinfunction "ID_ID") (pintype "bidirectional"))
    )
  )
)
